# POWER.net
KiCad netlist of a schematic drawn in Altium Designer
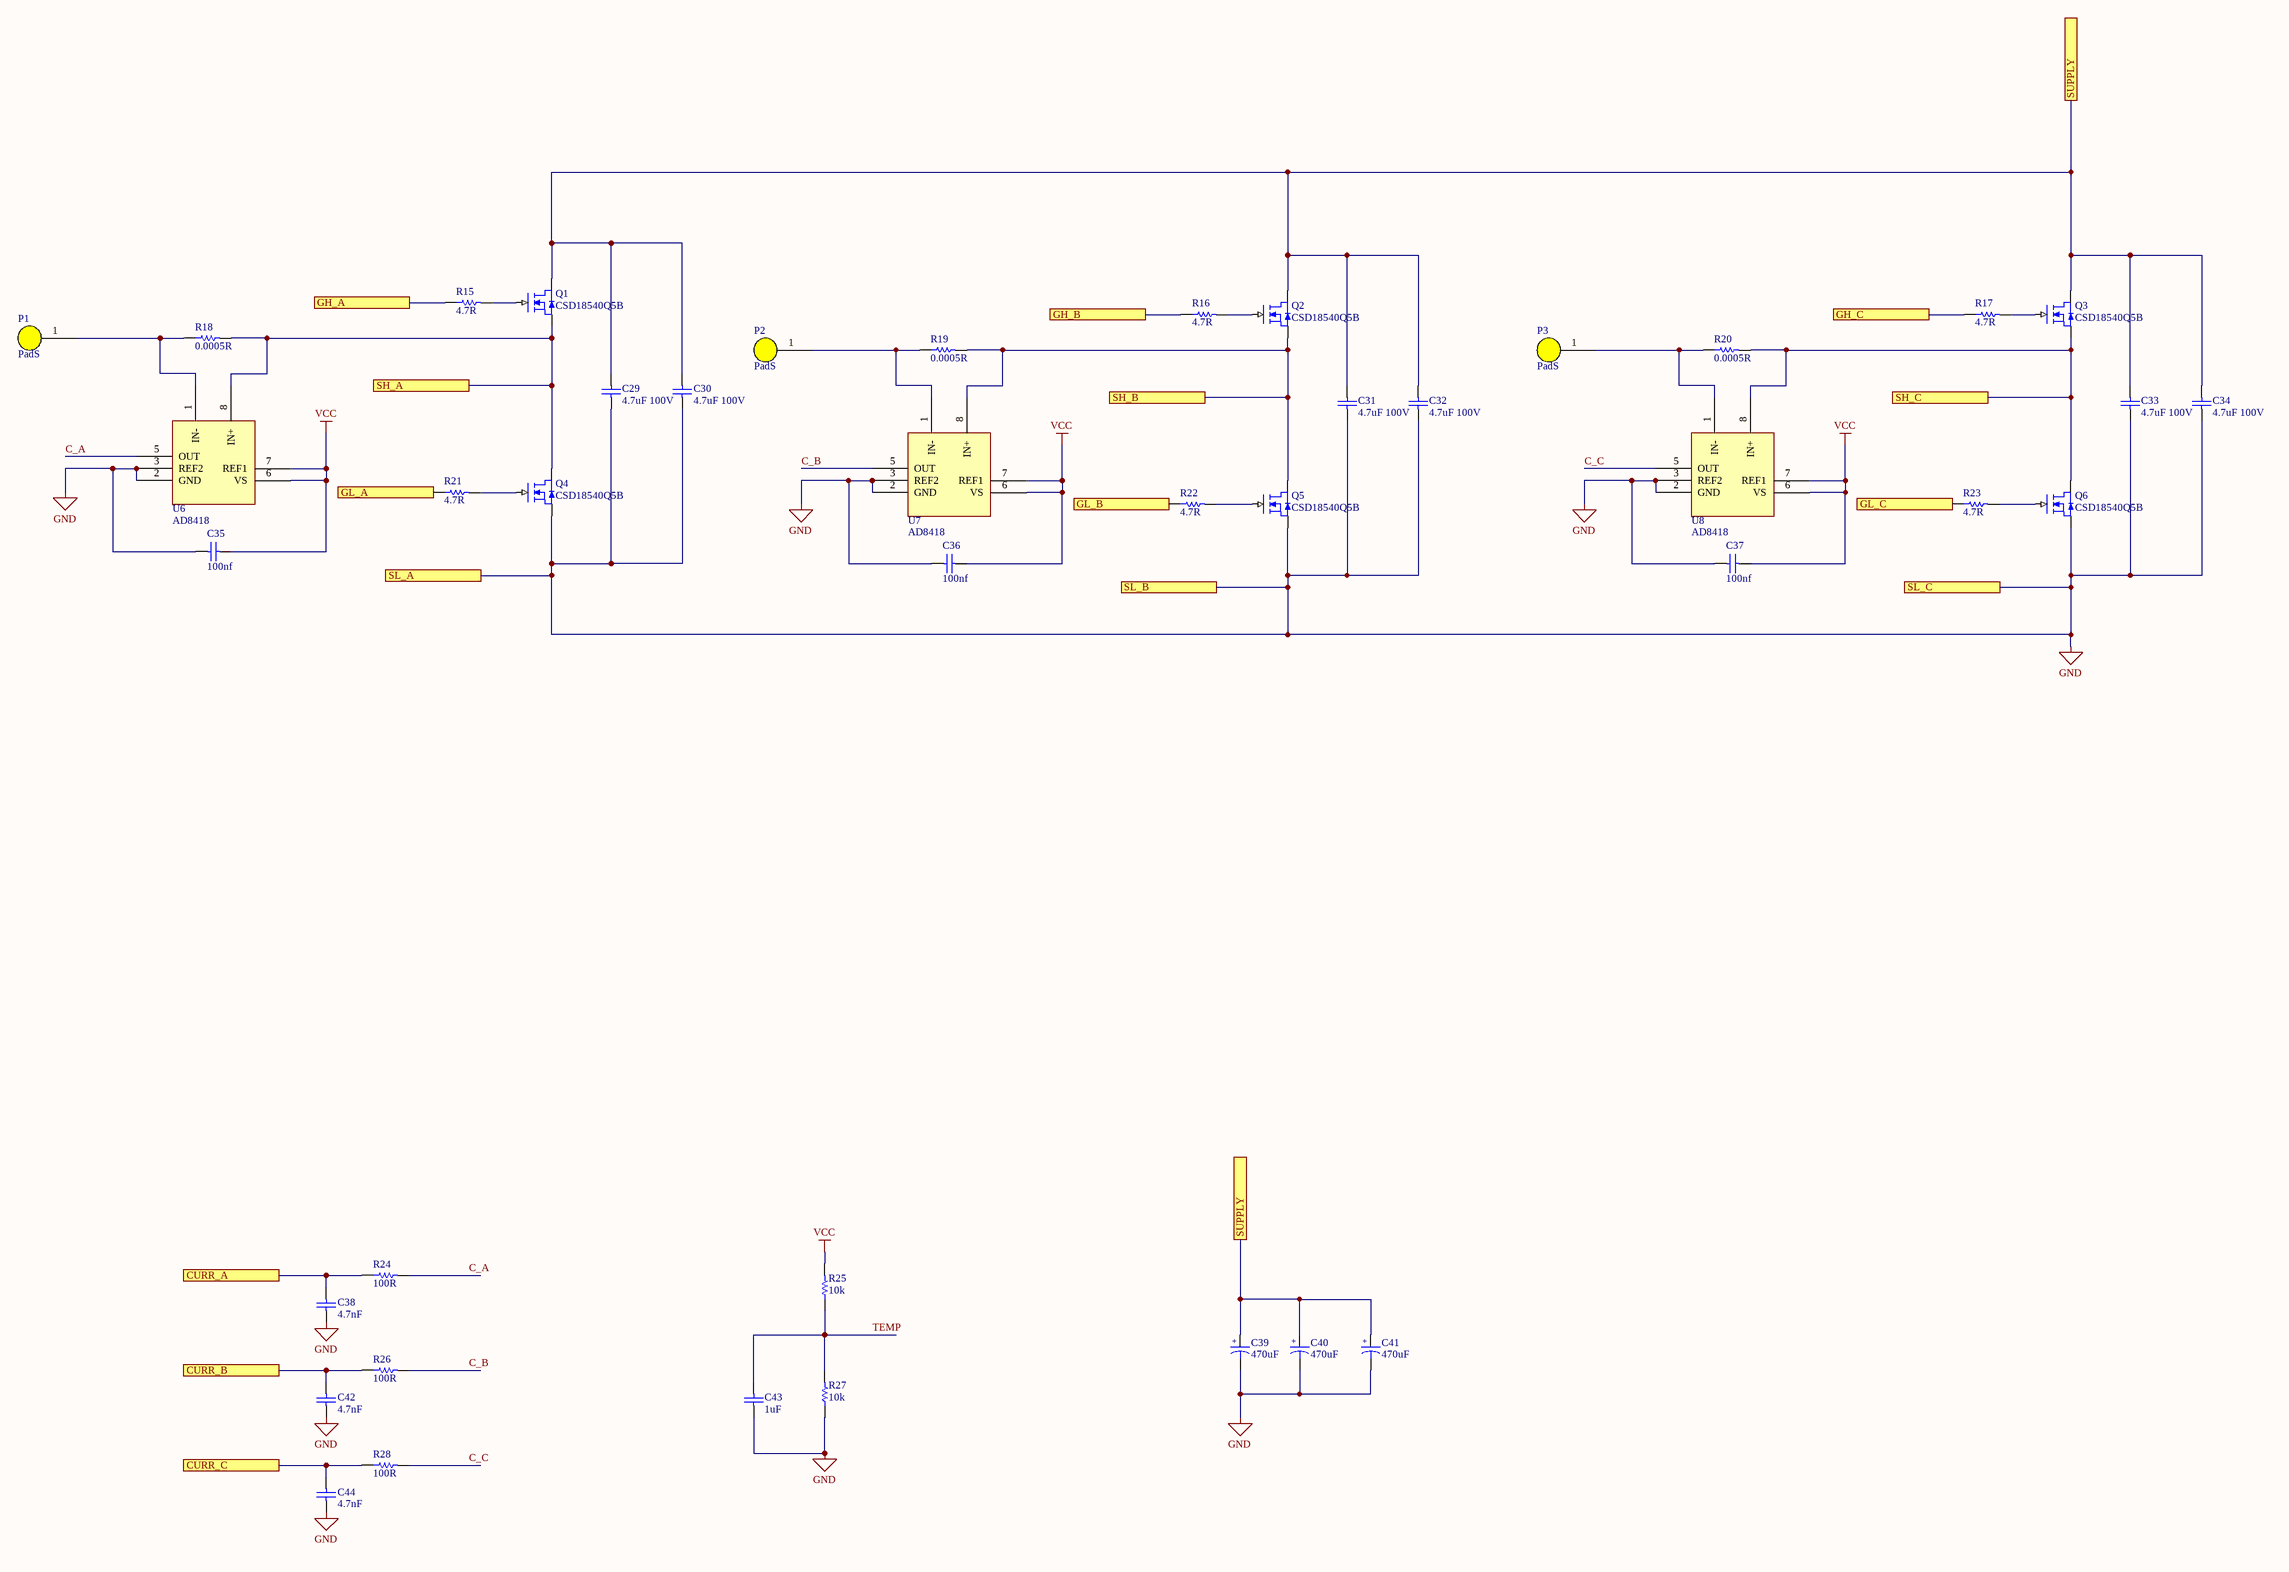
[diagram p0: POWER.SchDoc]

(export (version "E")
  (design (tool "Eeschema 10.0.6"))
  (components
    (comp (ref "C29")
      (value "4.7uF 100V")
      (footprint "1210")
      (description "Capacitor")
      (fields (field (name "PUBLISHER") "Altium Limited"))
      (libsource (lib "My Footprint") (part "CAP"))
    )
    (comp (ref "C30")
      (value "4.7uF 100V")
      (footprint "1210")
      (description "Capacitor")
      (fields (field (name "PUBLISHER") "Altium Limited"))
      (libsource (lib "My Footprint") (part "CAP"))
    )
    (comp (ref "C31")
      (value "4.7uF 100V")
      (footprint "1210")
      (description "Capacitor")
      (fields (field (name "PUBLISHER") "Altium Limited"))
      (libsource (lib "My Footprint") (part "CAP"))
    )
    (comp (ref "C32")
      (value "4.7uF 100V")
      (footprint "1210")
      (description "Capacitor")
      (fields (field (name "PUBLISHER") "Altium Limited"))
      (libsource (lib "My Footprint") (part "CAP"))
    )
    (comp (ref "C33")
      (value "4.7uF 100V")
      (footprint "1210")
      (description "Capacitor")
      (fields (field (name "PUBLISHER") "Altium Limited"))
      (libsource (lib "My Footprint") (part "CAP"))
    )
    (comp (ref "C34")
      (value "4.7uF 100V")
      (footprint "1210")
      (description "Capacitor")
      (fields (field (name "PUBLISHER") "Altium Limited"))
      (libsource (lib "My Footprint") (part "CAP"))
    )
    (comp (ref "C35")
      (value "100nf")
      (footprint "0603-1")
      (description "Capacitor")
      (fields (field (name "PUBLISHER") "Altium Limited"))
      (libsource (lib "My Footprint") (part "CAP"))
    )
    (comp (ref "C36")
      (value "100nf")
      (footprint "0603-1")
      (description "Capacitor")
      (fields (field (name "PUBLISHER") "Altium Limited"))
      (libsource (lib "My Footprint") (part "CAP"))
    )
    (comp (ref "C37")
      (value "100nf")
      (footprint "0603-1")
      (description "Capacitor")
      (fields (field (name "PUBLISHER") "Altium Limited"))
      (libsource (lib "My Footprint") (part "CAP"))
    )
    (comp (ref "C38")
      (value "4.7nF")
      (footprint "0603-1")
      (description "Capacitor")
      (fields (field (name "PUBLISHER") "Altium Limited"))
      (libsource (lib "My Footprint") (part "CAP"))
    )
    (comp (ref "C39") (value "470uF") (footprint "大电容") (libsource (lib "My Footprint") (part "CAP1")))
    (comp (ref "C40") (value "470uF") (footprint "大电容") (libsource (lib "My Footprint") (part "CAP1")))
    (comp (ref "C41") (value "470uF") (footprint "大电容") (libsource (lib "My Footprint") (part "CAP1")))
    (comp (ref "C42")
      (value "4.7nF")
      (footprint "0603-1")
      (description "Capacitor")
      (fields (field (name "PUBLISHER") "Altium Limited"))
      (libsource (lib "My Footprint") (part "CAP"))
    )
    (comp (ref "C43")
      (value "1uF")
      (footprint "0603-1")
      (description "Capacitor")
      (fields (field (name "PUBLISHER") "Altium Limited"))
      (libsource (lib "My Footprint") (part "CAP"))
    )
    (comp (ref "C44")
      (value "4.7nF")
      (footprint "0603-1")
      (description "Capacitor")
      (fields (field (name "PUBLISHER") "Altium Limited"))
      (libsource (lib "My Footprint") (part "CAP"))
    )
    (comp (ref "P1") (value "PadS") (footprint "MOTOR_PAD") (libsource (lib "VESC6 V1.0") (part "PadS")))
    (comp (ref "P2") (value "PadS") (footprint "MOTOR_PAD") (libsource (lib "VESC6 V1.0") (part "PadS")))
    (comp (ref "P3") (value "PadS") (footprint "MOTOR_PAD") (libsource (lib "VESC6 V1.0") (part "PadS")))
    (comp (ref "Q1")
      (value "CSD18540Q5B")
      (footprint "DFN5X6")
      (libsource (lib "TAOXUN") (part "CSD18540Q5B"))
    )
    (comp (ref "Q2")
      (value "CSD18540Q5B")
      (footprint "DFN5X6")
      (libsource (lib "TAOXUN") (part "CSD18540Q5B"))
    )
    (comp (ref "Q3")
      (value "CSD18540Q5B")
      (footprint "DFN5X6")
      (libsource (lib "TAOXUN") (part "CSD18540Q5B"))
    )
    (comp (ref "Q4")
      (value "CSD18540Q5B")
      (footprint "DFN5X6")
      (libsource (lib "TAOXUN") (part "CSD18540Q5B"))
    )
    (comp (ref "Q5")
      (value "CSD18540Q5B")
      (footprint "DFN5X6")
      (libsource (lib "TAOXUN") (part "CSD18540Q5B"))
    )
    (comp (ref "Q6")
      (value "CSD18540Q5B")
      (footprint "DFN5X6")
      (libsource (lib "TAOXUN") (part "CSD18540Q5B"))
    )
    (comp (ref "R15")
      (value "4.7R")
      (footprint "0603-1")
      (description "Resistor")
      (fields (field (name "PUBLISHER") "Altium Limited"))
      (libsource (lib "My Footprint") (part "RES"))
    )
    (comp (ref "R16")
      (value "4.7R")
      (footprint "0603-1")
      (description "Resistor")
      (fields (field (name "PUBLISHER") "Altium Limited"))
      (libsource (lib "My Footprint") (part "RES"))
    )
    (comp (ref "R17")
      (value "4.7R")
      (footprint "0603-1")
      (description "Resistor")
      (fields (field (name "PUBLISHER") "Altium Limited"))
      (libsource (lib "My Footprint") (part "RES"))
    )
    (comp (ref "R18")
      (value "0.0005R")
      (footprint "采样电阻0.0005R")
      (description "Resistor")
      (fields (field (name "PUBLISHER") "Altium Limited"))
      (libsource (lib "My Footprint") (part "RES"))
    )
    (comp (ref "R19")
      (value "0.0005R")
      (footprint "采样电阻0.0005R")
      (description "Resistor")
      (fields (field (name "PUBLISHER") "Altium Limited"))
      (libsource (lib "My Footprint") (part "RES"))
    )
    (comp (ref "R20")
      (value "0.0005R")
      (footprint "采样电阻0.0005R")
      (description "Resistor")
      (fields (field (name "PUBLISHER") "Altium Limited"))
      (libsource (lib "My Footprint") (part "RES"))
    )
    (comp (ref "R21")
      (value "4.7R")
      (footprint "0603-1")
      (description "Resistor")
      (fields (field (name "PUBLISHER") "Altium Limited"))
      (libsource (lib "My Footprint") (part "RES"))
    )
    (comp (ref "R22")
      (value "4.7R")
      (footprint "0603-1")
      (description "Resistor")
      (fields (field (name "PUBLISHER") "Altium Limited"))
      (libsource (lib "My Footprint") (part "RES"))
    )
    (comp (ref "R23")
      (value "4.7R")
      (footprint "0603-1")
      (description "Resistor")
      (fields (field (name "PUBLISHER") "Altium Limited"))
      (libsource (lib "My Footprint") (part "RES"))
    )
    (comp (ref "R24")
      (value "100R")
      (footprint "0603-1")
      (description "Resistor")
      (fields (field (name "PUBLISHER") "Altium Limited"))
      (libsource (lib "My Footprint") (part "RES"))
    )
    (comp (ref "R25")
      (value "10k")
      (footprint "0603-1")
      (description "Resistor")
      (fields (field (name "PUBLISHER") "Altium Limited"))
      (libsource (lib "My Footprint") (part "RES"))
    )
    (comp (ref "R26")
      (value "100R")
      (footprint "0603-1")
      (description "Resistor")
      (fields (field (name "PUBLISHER") "Altium Limited"))
      (libsource (lib "My Footprint") (part "RES"))
    )
    (comp (ref "R27")
      (value "10k")
      (footprint "0603-1")
      (description "Resistor")
      (fields (field (name "PUBLISHER") "Altium Limited"))
      (libsource (lib "My Footprint") (part "RES"))
    )
    (comp (ref "R28")
      (value "100R")
      (footprint "0603-1")
      (description "Resistor")
      (fields (field (name "PUBLISHER") "Altium Limited"))
      (libsource (lib "My Footprint") (part "RES"))
    )
    (comp (ref "U6")
      (value "AD8418")
      (footprint "SOP8-TJA1050")
      (libsource (lib "VESC6 V1.0") (part "AD8418"))
    )
    (comp (ref "U7")
      (value "AD8418")
      (footprint "SOP8-TJA1050")
      (libsource (lib "VESC6 V1.0") (part "AD8418"))
    )
    (comp (ref "U8")
      (value "AD8418")
      (footprint "SOP8-TJA1050")
      (libsource (lib "VESC6 V1.0") (part "AD8418"))
    )
  )
  (nets
    (net (code "1") (name "/CURR_A") (class "Default")
      (node (ref "C38") (pin "2") (pinfunction "2_2") (pintype "passive"))
      (node (ref "R24") (pin "1") (pinfunction "1_1") (pintype "passive"))
    )
    (net (code "2") (name "/CURR_B") (class "Default")
      (node (ref "C42") (pin "2") (pinfunction "2_2") (pintype "passive"))
      (node (ref "R26") (pin "1") (pinfunction "1_1") (pintype "passive"))
    )
    (net (code "3") (name "/CURR_C") (class "Default")
      (node (ref "C44") (pin "2") (pinfunction "2_2") (pintype "passive"))
      (node (ref "R28") (pin "1") (pinfunction "1_1") (pintype "passive"))
    )
    (net (code "4") (name "/C_A") (class "Default")
      (node (ref "R24") (pin "2") (pinfunction "2_2") (pintype "passive"))
      (node (ref "U6") (pin "5") (pinfunction "OUT_5") (pintype "passive"))
    )
    (net (code "5") (name "/C_B") (class "Default")
      (node (ref "R26") (pin "2") (pinfunction "2_2") (pintype "passive"))
      (node (ref "U7") (pin "5") (pinfunction "OUT_5") (pintype "passive"))
    )
    (net (code "6") (name "/C_C") (class "Default")
      (node (ref "R28") (pin "2") (pinfunction "2_2") (pintype "passive"))
      (node (ref "U8") (pin "5") (pinfunction "OUT_5") (pintype "passive"))
    )
    (net (code "7") (name "/GH_A") (class "Default")
      (node (ref "R15") (pin "1") (pinfunction "1_1") (pintype "passive"))
    )
    (net (code "8") (name "/GH_B") (class "Default")
      (node (ref "R16") (pin "1") (pinfunction "1_1") (pintype "passive"))
    )
    (net (code "9") (name "/GH_C") (class "Default")
      (node (ref "R17") (pin "1") (pinfunction "1_1") (pintype "passive"))
    )
    (net (code "10") (name "/GL_A") (class "Default")
      (node (ref "R21") (pin "1") (pinfunction "1_1") (pintype "passive"))
    )
    (net (code "11") (name "/GL_B") (class "Default")
      (node (ref "R22") (pin "1") (pinfunction "1_1") (pintype "passive"))
    )
    (net (code "12") (name "/GL_C") (class "Default")
      (node (ref "R23") (pin "1") (pinfunction "1_1") (pintype "passive"))
    )
    (net (code "13") (name "/SH_A") (class "Default")
      (node (ref "Q1") (pin "1") (pinfunction "S_1") (pintype "power_in"))
      (node (ref "Q4") (pin "8") (pinfunction "D_8") (pintype "power_in"))
      (node (ref "R18") (pin "2") (pinfunction "2_2") (pintype "passive"))
      (node (ref "U6") (pin "8") (pinfunction "IN+_8") (pintype "passive"))
    )
    (net (code "14") (name "/SH_B") (class "Default")
      (node (ref "Q2") (pin "1") (pinfunction "S_1") (pintype "power_in"))
      (node (ref "Q5") (pin "8") (pinfunction "D_8") (pintype "power_in"))
      (node (ref "R19") (pin "2") (pinfunction "2_2") (pintype "passive"))
      (node (ref "U7") (pin "8") (pinfunction "IN+_8") (pintype "passive"))
    )
    (net (code "15") (name "/SH_C") (class "Default")
      (node (ref "Q3") (pin "1") (pinfunction "S_1") (pintype "power_in"))
      (node (ref "Q6") (pin "8") (pinfunction "D_8") (pintype "power_in"))
      (node (ref "R20") (pin "2") (pinfunction "2_2") (pintype "passive"))
      (node (ref "U8") (pin "8") (pinfunction "IN+_8") (pintype "passive"))
    )
    (net (code "16") (name "/SUPPLY") (class "Default")
      (node (ref "C29") (pin "1") (pinfunction "1_1") (pintype "passive"))
      (node (ref "C30") (pin "1") (pinfunction "1_1") (pintype "passive"))
      (node (ref "C31") (pin "1") (pinfunction "1_1") (pintype "passive"))
      (node (ref "C32") (pin "1") (pinfunction "1_1") (pintype "passive"))
      (node (ref "C33") (pin "1") (pinfunction "1_1") (pintype "passive"))
      (node (ref "C34") (pin "1") (pinfunction "1_1") (pintype "passive"))
      (node (ref "C39") (pin "1") (pinfunction "1_1") (pintype "passive"))
      (node (ref "C40") (pin "1") (pinfunction "1_1") (pintype "passive"))
      (node (ref "C41") (pin "1") (pinfunction "1_1") (pintype "passive"))
      (node (ref "Q1") (pin "8") (pinfunction "D_8") (pintype "power_in"))
      (node (ref "Q2") (pin "8") (pinfunction "D_8") (pintype "power_in"))
      (node (ref "Q3") (pin "8") (pinfunction "D_8") (pintype "power_in"))
    )
    (net (code "17") (name "/TEMP") (class "Default")
      (node (ref "C43") (pin "2") (pinfunction "2_2") (pintype "passive"))
      (node (ref "R25") (pin "1") (pinfunction "1_1") (pintype "passive"))
      (node (ref "R27") (pin "2") (pinfunction "2_2") (pintype "passive"))
    )
    (net (code "18") (name "GND") (class "Default")
      (node (ref "C29") (pin "2") (pinfunction "2_2") (pintype "passive"))
      (node (ref "C30") (pin "2") (pinfunction "2_2") (pintype "passive"))
      (node (ref "C31") (pin "2") (pinfunction "2_2") (pintype "passive"))
      (node (ref "C32") (pin "2") (pinfunction "2_2") (pintype "passive"))
      (node (ref "C33") (pin "2") (pinfunction "2_2") (pintype "passive"))
      (node (ref "C34") (pin "2") (pinfunction "2_2") (pintype "passive"))
      (node (ref "C35") (pin "2") (pinfunction "2_2") (pintype "passive"))
      (node (ref "C36") (pin "2") (pinfunction "2_2") (pintype "passive"))
      (node (ref "C37") (pin "2") (pinfunction "2_2") (pintype "passive"))
      (node (ref "C38") (pin "1") (pinfunction "1_1") (pintype "passive"))
      (node (ref "C39") (pin "2") (pinfunction "2_2") (pintype "passive"))
      (node (ref "C40") (pin "2") (pinfunction "2_2") (pintype "passive"))
      (node (ref "C41") (pin "2") (pinfunction "2_2") (pintype "passive"))
      (node (ref "C42") (pin "1") (pinfunction "1_1") (pintype "passive"))
      (node (ref "C43") (pin "1") (pinfunction "1_1") (pintype "passive"))
      (node (ref "C44") (pin "1") (pinfunction "1_1") (pintype "passive"))
      (node (ref "Q4") (pin "1") (pinfunction "S_1") (pintype "power_in"))
      (node (ref "Q5") (pin "1") (pinfunction "S_1") (pintype "power_in"))
      (node (ref "Q6") (pin "1") (pinfunction "S_1") (pintype "power_in"))
      (node (ref "R27") (pin "1") (pinfunction "1_1") (pintype "passive"))
      (node (ref "U6") (pin "2") (pinfunction "GND_2") (pintype "passive"))
      (node (ref "U6") (pin "3") (pinfunction "REF2_3") (pintype "passive"))
      (node (ref "U7") (pin "2") (pinfunction "GND_2") (pintype "passive"))
      (node (ref "U7") (pin "3") (pinfunction "REF2_3") (pintype "passive"))
      (node (ref "U8") (pin "2") (pinfunction "GND_2") (pintype "passive"))
      (node (ref "U8") (pin "3") (pinfunction "REF2_3") (pintype "passive"))
    )
    (net (code "19") (name "Net-(P1-15)") (class "Default")
      (node (ref "P1") (pin "1") (pinfunction "15_1") (pintype "passive"))
      (node (ref "R18") (pin "1") (pinfunction "1_1") (pintype "passive"))
      (node (ref "U6") (pin "1") (pinfunction "IN-_1") (pintype "passive"))
    )
    (net (code "20") (name "Net-(P2-15)") (class "Default")
      (node (ref "P2") (pin "1") (pinfunction "15_1") (pintype "passive"))
      (node (ref "R19") (pin "1") (pinfunction "1_1") (pintype "passive"))
      (node (ref "U7") (pin "1") (pinfunction "IN-_1") (pintype "passive"))
    )
    (net (code "21") (name "Net-(P3-15)") (class "Default")
      (node (ref "P3") (pin "1") (pinfunction "15_1") (pintype "passive"))
      (node (ref "R20") (pin "1") (pinfunction "1_1") (pintype "passive"))
      (node (ref "U8") (pin "1") (pinfunction "IN-_1") (pintype "passive"))
    )
    (net (code "22") (name "Net-(Q1-G)") (class "Default")
      (node (ref "Q1") (pin "4") (pinfunction "G_4") (pintype "input"))
      (node (ref "R15") (pin "2") (pinfunction "2_2") (pintype "passive"))
    )
    (net (code "23") (name "Net-(Q2-G)") (class "Default")
      (node (ref "Q2") (pin "4") (pinfunction "G_4") (pintype "input"))
      (node (ref "R16") (pin "2") (pinfunction "2_2") (pintype "passive"))
    )
    (net (code "24") (name "Net-(Q3-G)") (class "Default")
      (node (ref "Q3") (pin "4") (pinfunction "G_4") (pintype "input"))
      (node (ref "R17") (pin "2") (pinfunction "2_2") (pintype "passive"))
    )
    (net (code "25") (name "Net-(Q4-G)") (class "Default")
      (node (ref "Q4") (pin "4") (pinfunction "G_4") (pintype "input"))
      (node (ref "R21") (pin "2") (pinfunction "2_2") (pintype "passive"))
    )
    (net (code "26") (name "Net-(Q5-G)") (class "Default")
      (node (ref "Q5") (pin "4") (pinfunction "G_4") (pintype "input"))
      (node (ref "R22") (pin "2") (pinfunction "2_2") (pintype "passive"))
    )
    (net (code "27") (name "Net-(Q6-G)") (class "Default")
      (node (ref "Q6") (pin "4") (pinfunction "G_4") (pintype "input"))
      (node (ref "R23") (pin "2") (pinfunction "2_2") (pintype "passive"))
    )
    (net (code "28") (name "VCC") (class "Default")
      (node (ref "C35") (pin "1") (pinfunction "1_1") (pintype "passive"))
      (node (ref "C36") (pin "1") (pinfunction "1_1") (pintype "passive"))
      (node (ref "C37") (pin "1") (pinfunction "1_1") (pintype "passive"))
      (node (ref "R25") (pin "2") (pinfunction "2_2") (pintype "passive"))
      (node (ref "U6") (pin "6") (pinfunction "VS_6") (pintype "passive"))
      (node (ref "U6") (pin "7") (pinfunction "REF1_7") (pintype "passive"))
      (node (ref "U7") (pin "6") (pinfunction "VS_6") (pintype "passive"))
      (node (ref "U7") (pin "7") (pinfunction "REF1_7") (pintype "passive"))
      (node (ref "U8") (pin "6") (pinfunction "VS_6") (pintype "passive"))
      (node (ref "U8") (pin "7") (pinfunction "REF1_7") (pintype "passive"))
    )
  )
)
